# Ver_Full.net
KiCad netlist of a schematic drawn in EAGLE
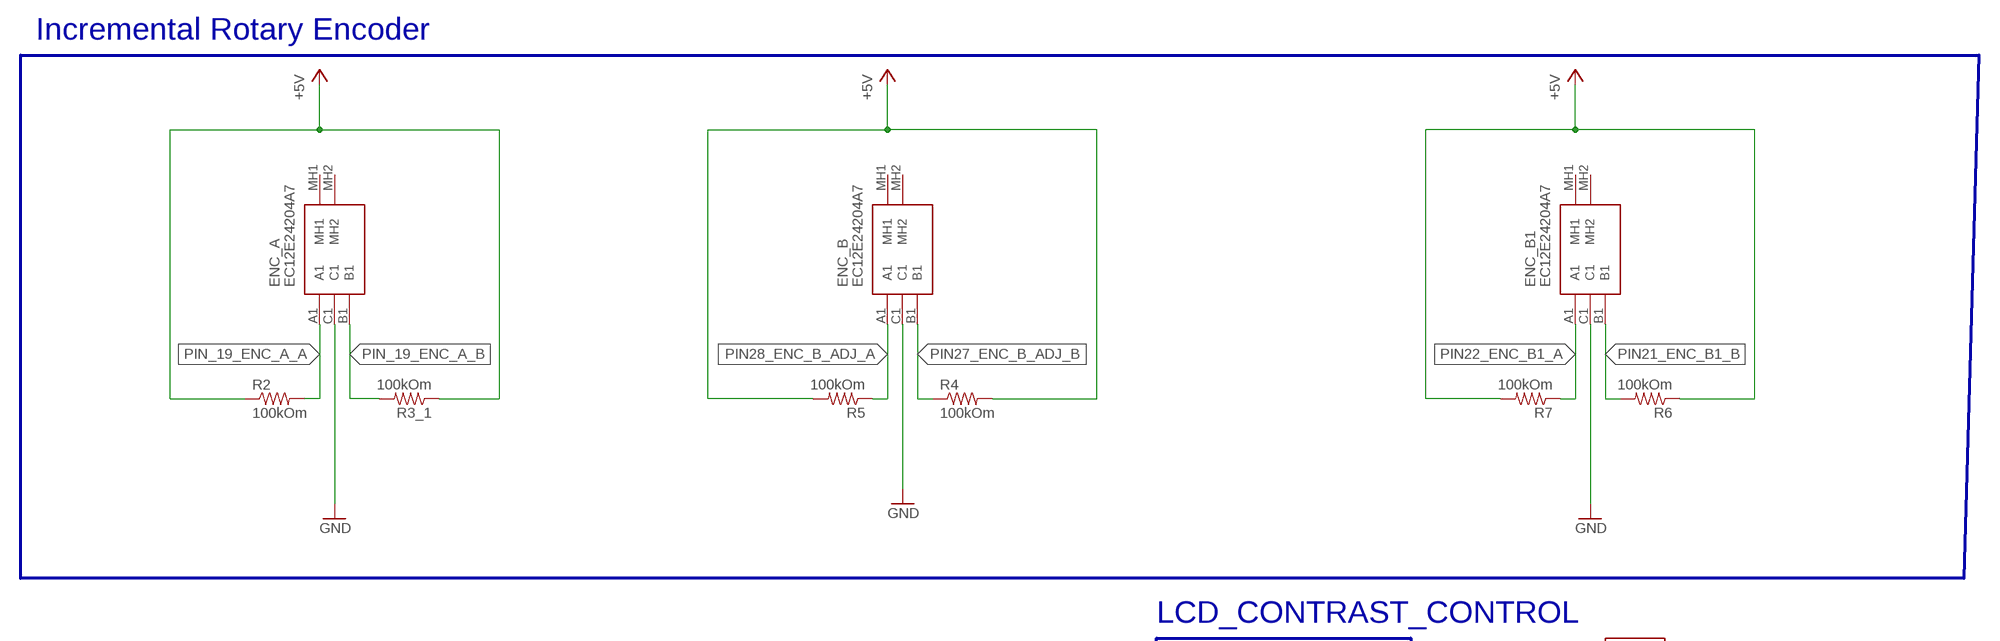
[diagram p0: schematic, sheet 1, part 1 of 3]
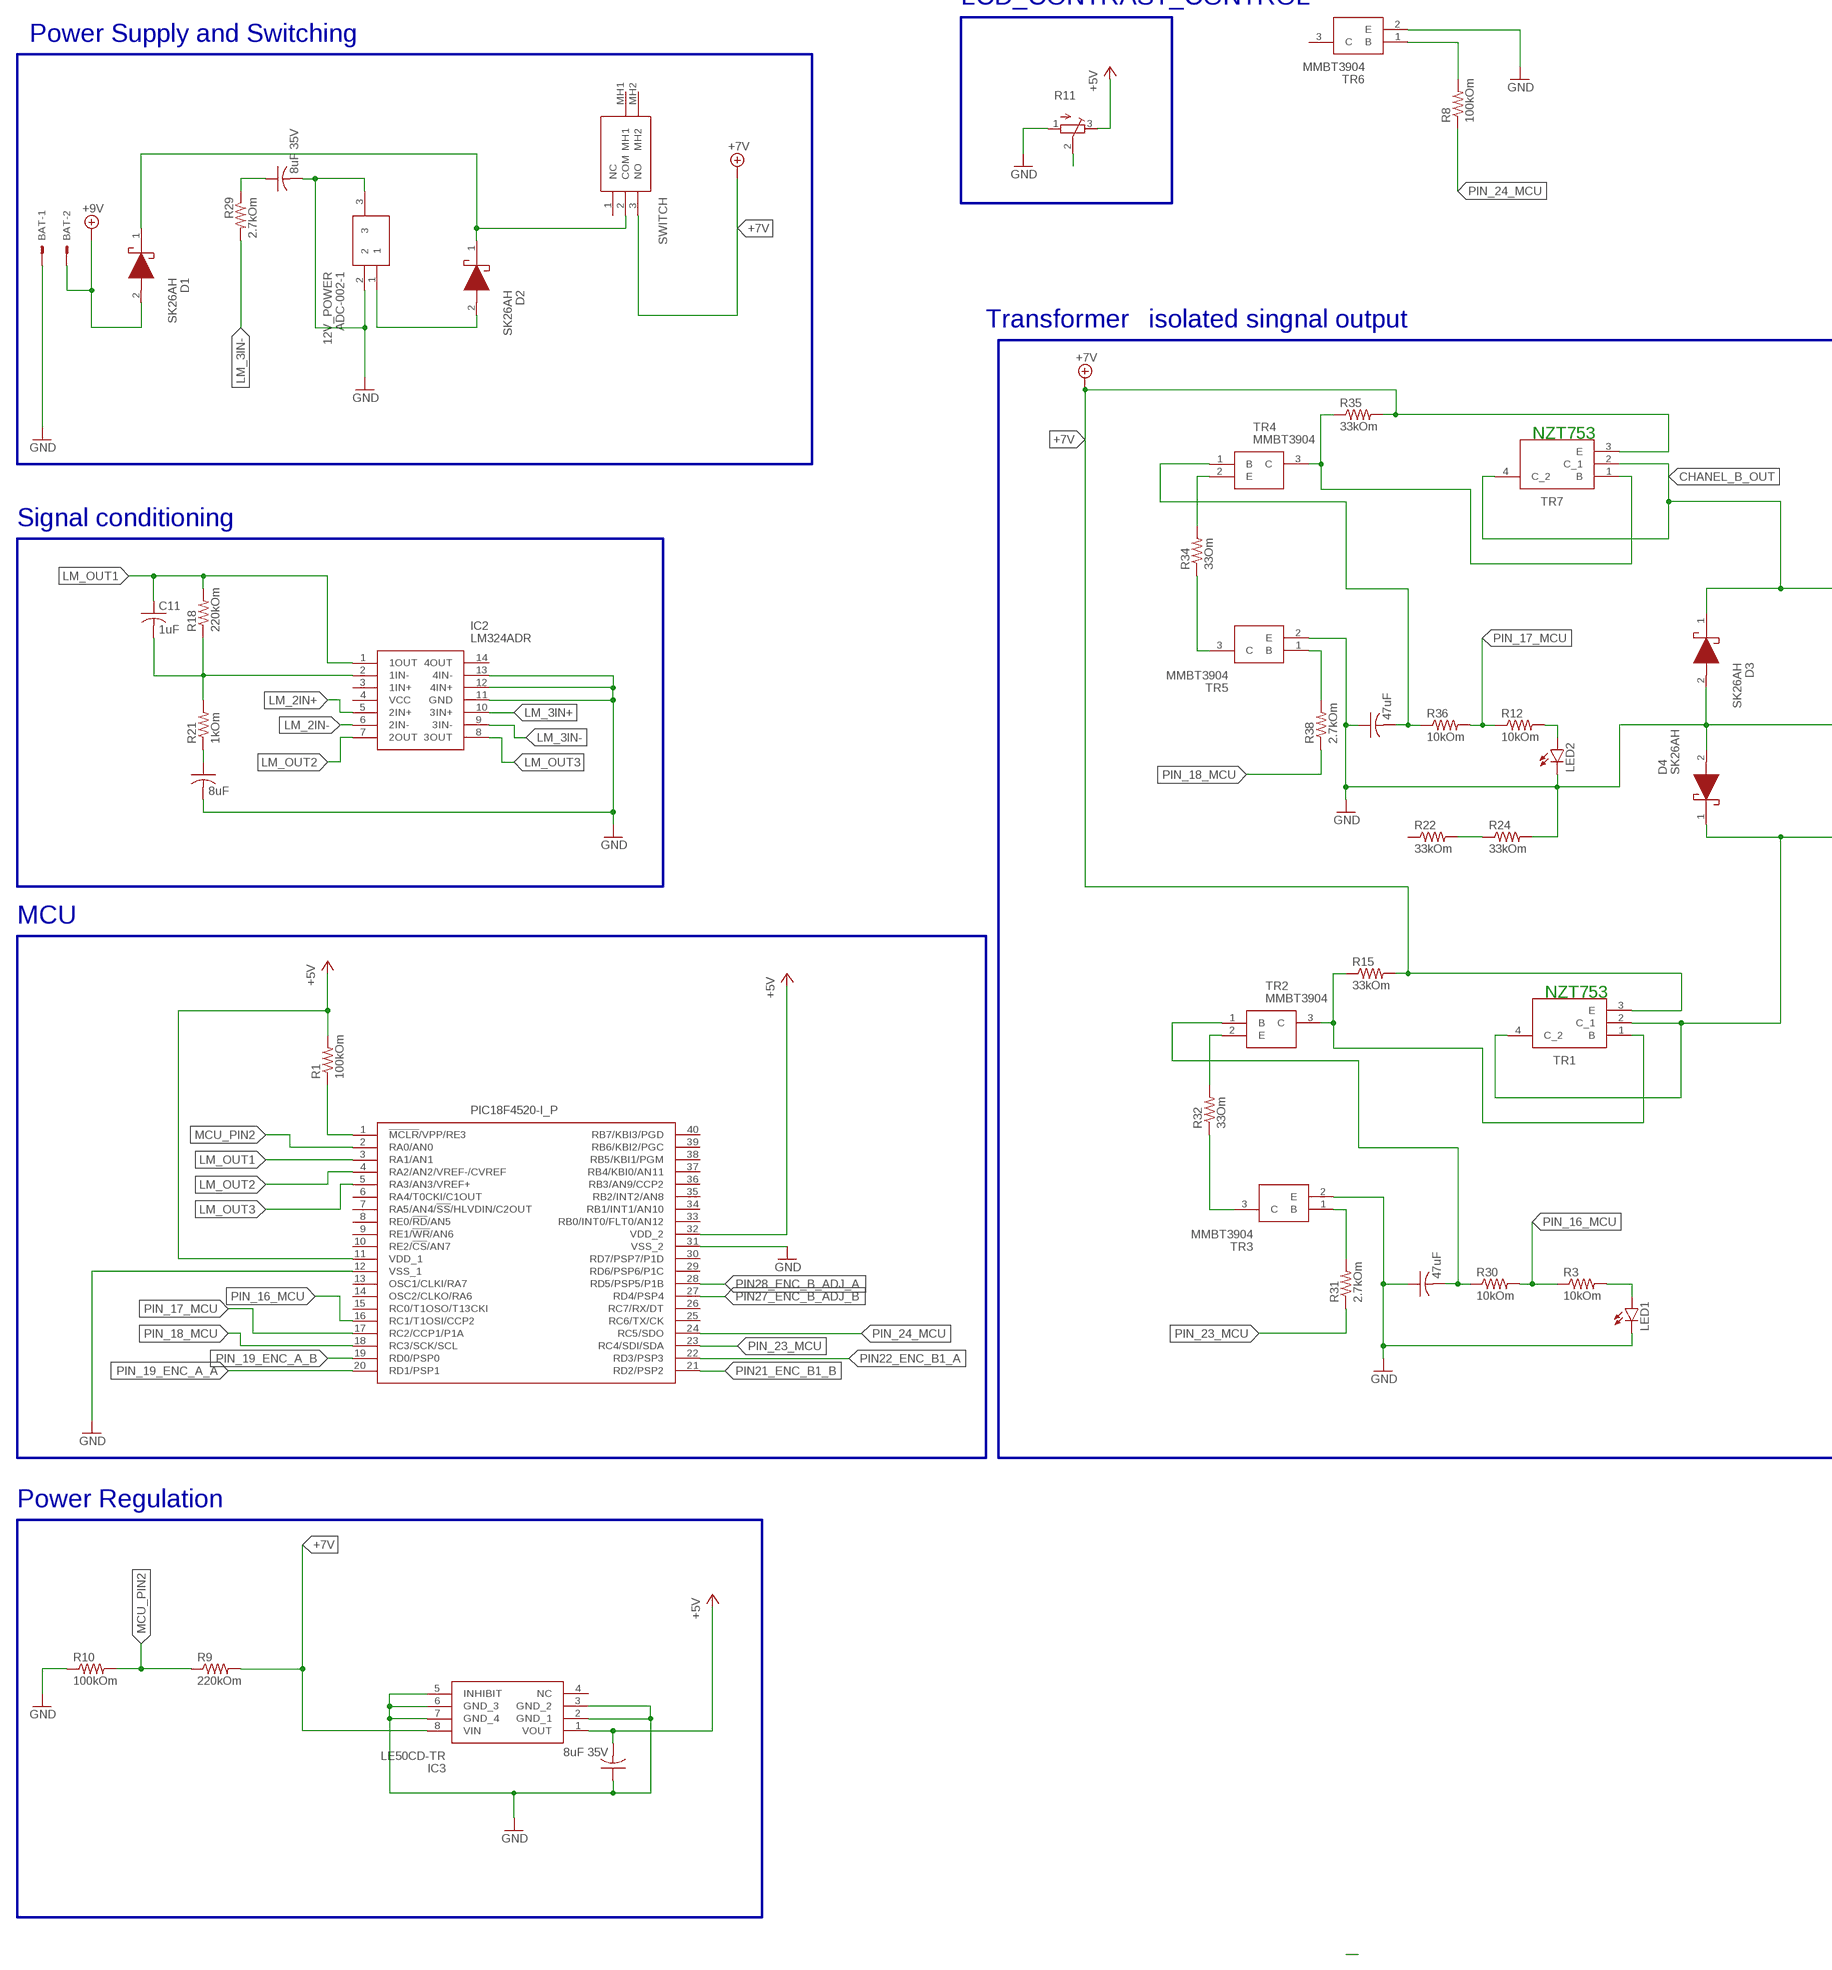
[diagram p1: schematic, sheet 1, part 2 of 3]
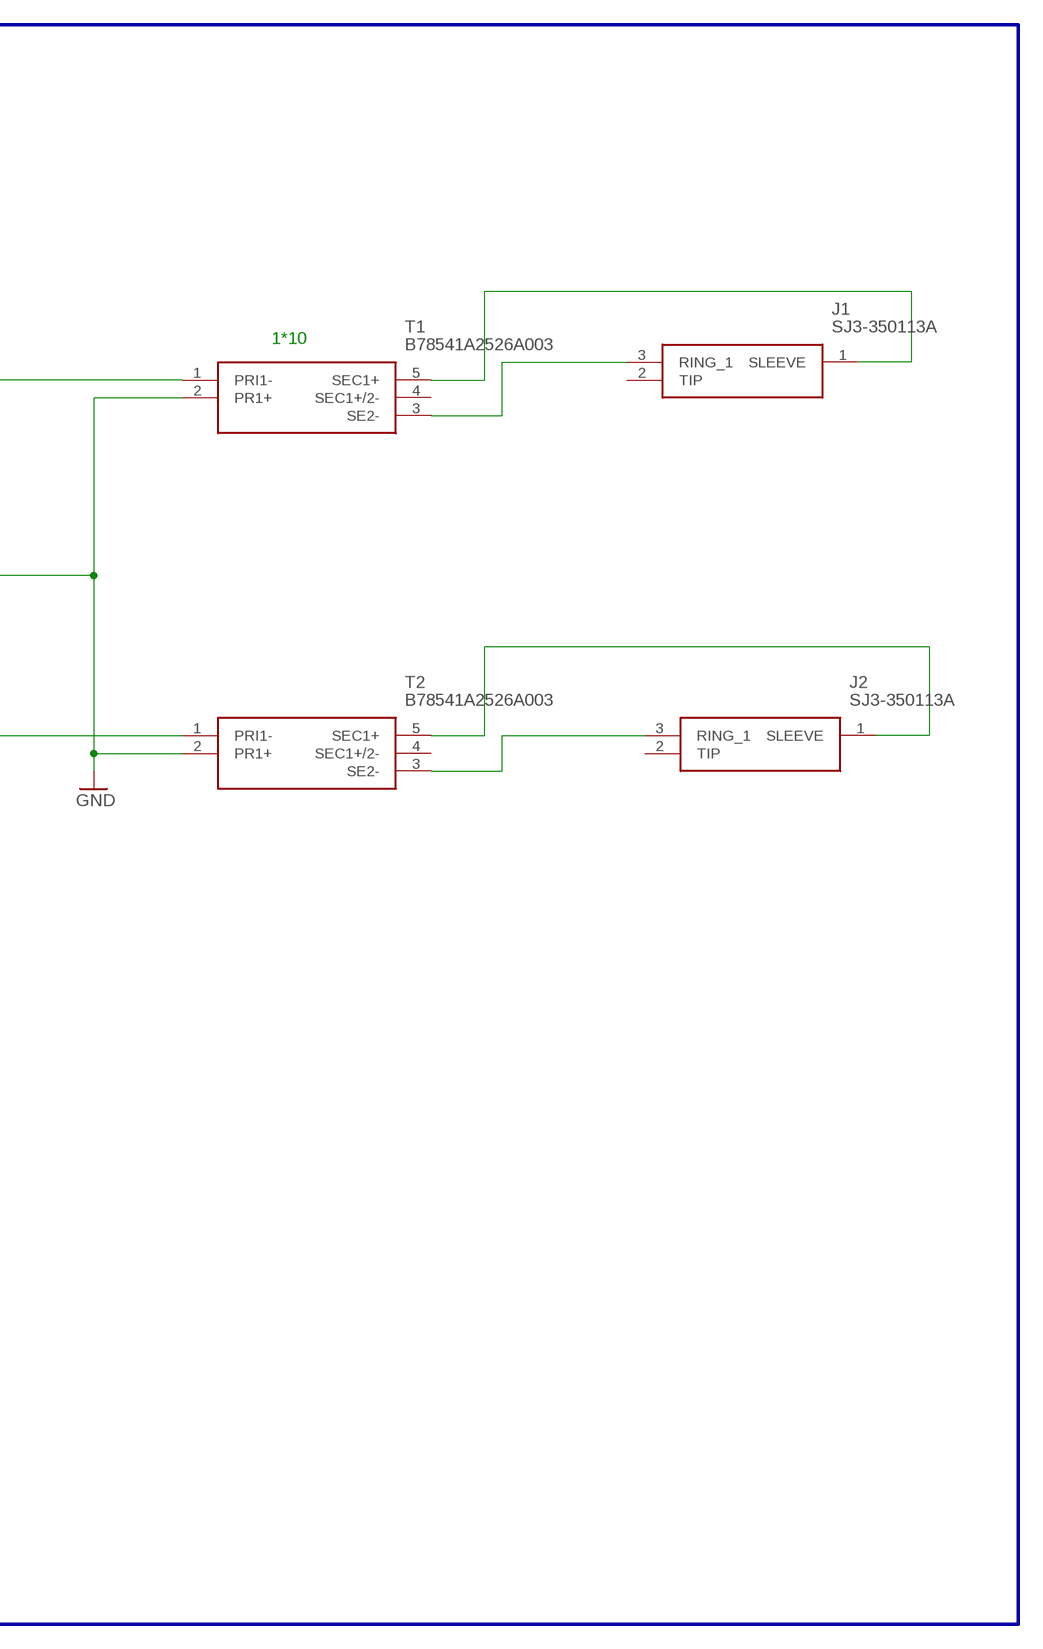
[diagram p2: schematic, sheet 1, part 3 of 3]
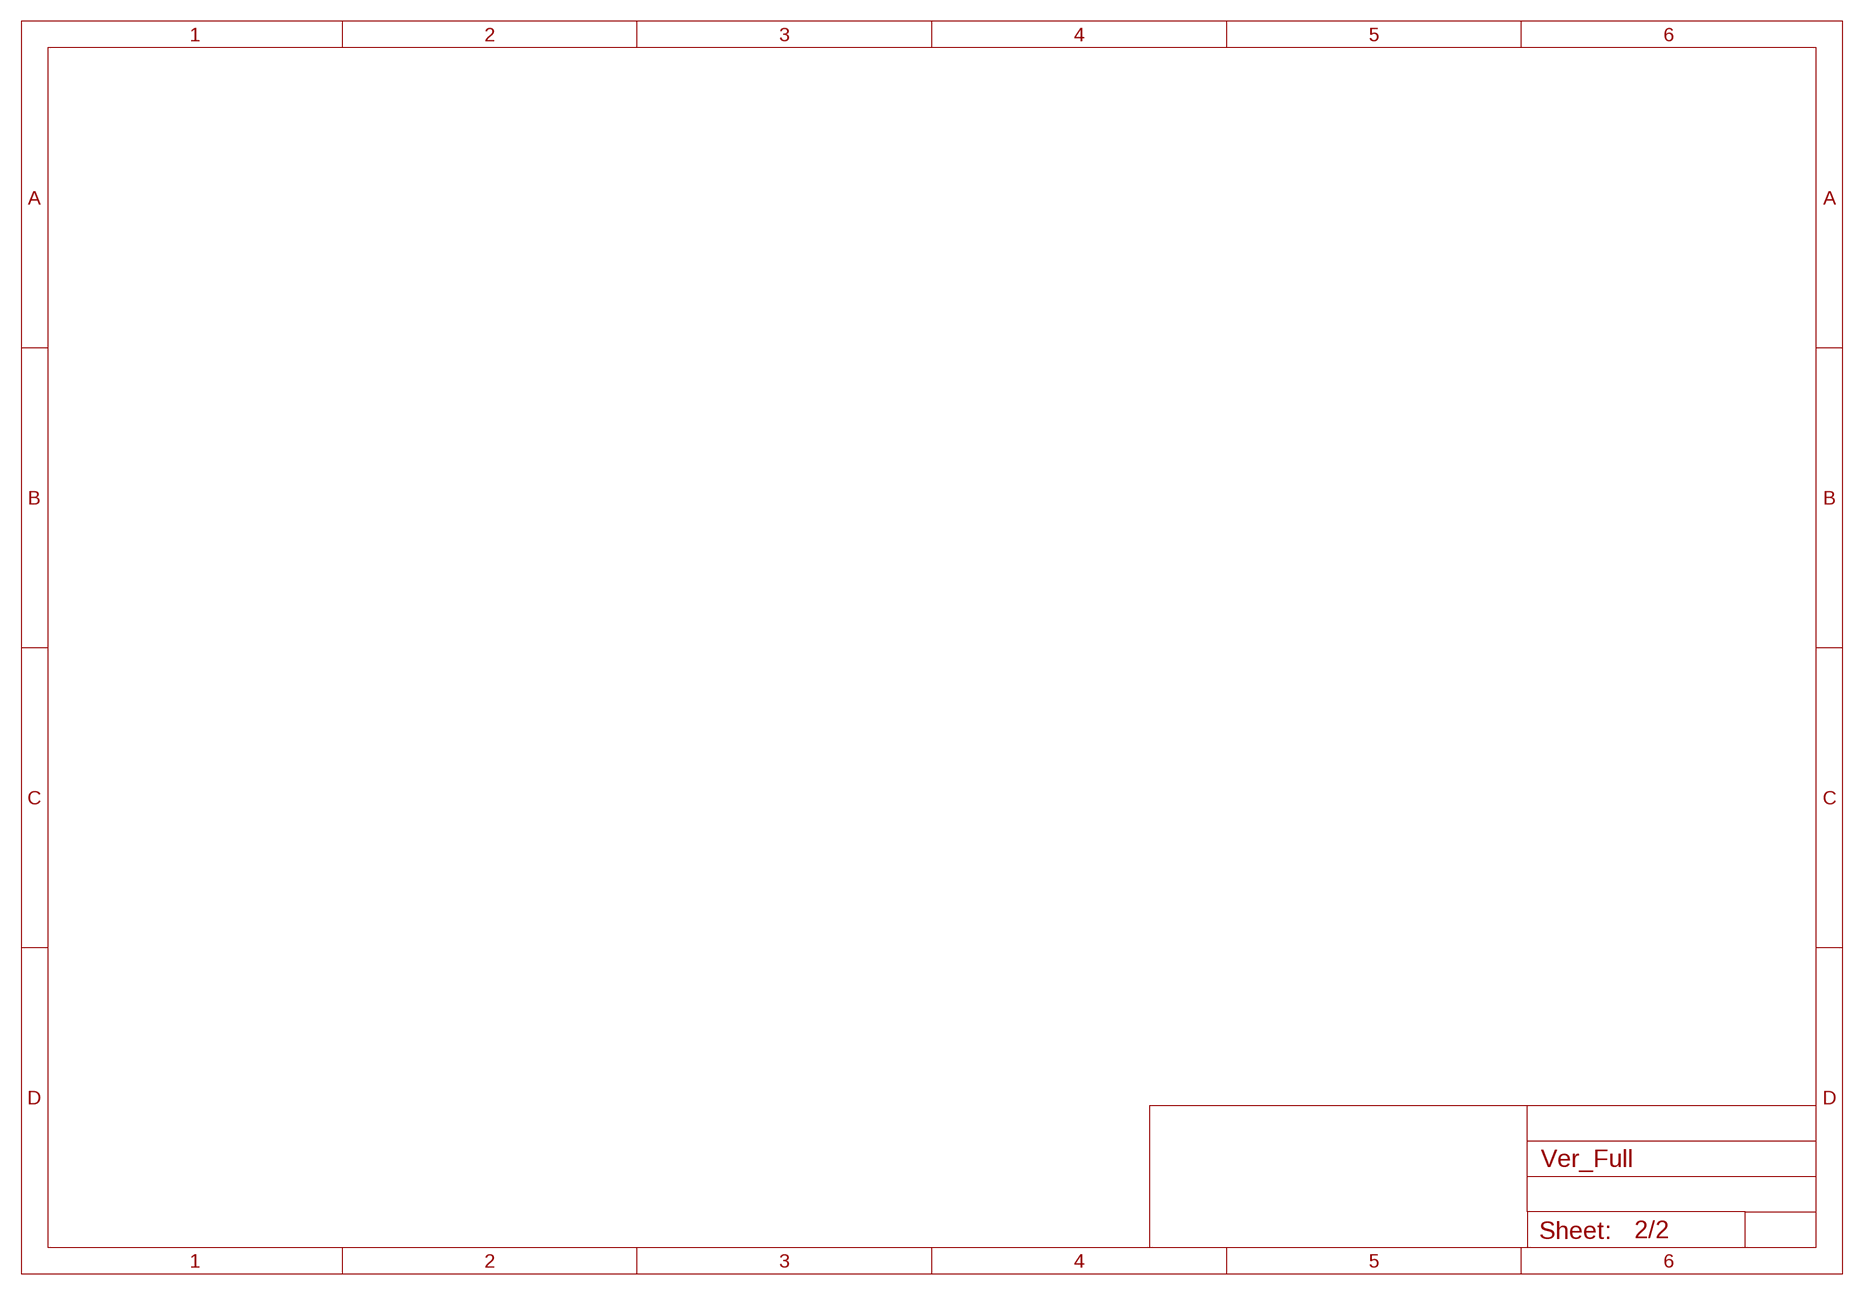
[diagram p3: schematic, sheet 2]

(export (version "E")
  (design (tool "Eeschema 10.0.6"))
  (components
    (comp (ref "12V_POWER")
      (value "ADC-002-1")
      (footprint "eagle-import:ADC0021")
      (fields (field (name "MOUSER_PART_NUMBER") "737-ADC-002-1"))
      (libsource (lib "eagle-import") (part "ADC-002-1"))
    )
    (comp (ref "BAT")
      (value "22-23-2021")
      (footprint "eagle-import:22-23-2021")
      (fields (field (name "MF") "MOLEX"))
      (libsource (lib "eagle-import") (part "22-23-2021"))
    )
    (comp (ref "C2")
      (value "8uF 35V")
      (footprint "eagle-import:C1608")
      (libsource (lib "eagle-import") (part "C-USC1608"))
    )
    (comp (ref "C3_1")
      (value "8uF 35V")
      (footprint "eagle-import:C1608")
      (libsource (lib "eagle-import") (part "C-USC1608"))
    )
    (comp (ref "C6")
      (value "8uF")
      (footprint "eagle-import:C1608")
      (libsource (lib "eagle-import") (part "C-USC1608"))
    )
    (comp (ref "C11")
      (value "1uF")
      (footprint "eagle-import:C0603")
      (libsource (lib "eagle-import") (part "C-USC0603"))
    )
    (comp (ref "C14")
      (value "47uF")
      (footprint "eagle-import:C1608")
      (libsource (lib "eagle-import") (part "C-USC1608"))
    )
    (comp (ref "C16")
      (value "47uF")
      (footprint "eagle-import:C1608")
      (libsource (lib "eagle-import") (part "C-USC1608"))
    )
    (comp (ref "D1")
      (value "SK26AH")
      (footprint "eagle-import:DIONM5126X250N")
      (fields (field (name "MOUSER_PART_NUMBER") "821-SK26AH"))
      (libsource (lib "eagle-import") (part "SK26AH"))
    )
    (comp (ref "D2")
      (value "SK26AH")
      (footprint "eagle-import:DIONM5126X250N")
      (fields (field (name "MOUSER_PART_NUMBER") "821-SK26AH"))
      (libsource (lib "eagle-import") (part "SK26AH"))
    )
    (comp (ref "D3")
      (value "SK26AH")
      (footprint "eagle-import:DIONM5126X250N")
      (fields (field (name "MOUSER_PART_NUMBER") "821-SK26AH"))
      (libsource (lib "eagle-import") (part "SK26AH"))
    )
    (comp (ref "D4")
      (value "SK26AH")
      (footprint "eagle-import:DIONM5126X250N")
      (fields (field (name "MOUSER_PART_NUMBER") "821-SK26AH"))
      (libsource (lib "eagle-import") (part "SK26AH"))
    )
    (comp (ref "ENC_A")
      (value "EC12E24204A7")
      (footprint "eagle-import:EC12E24204A7")
      (fields (field (name "MOUSER_PART_NUMBER") "688-EC12E24204A7"))
      (libsource (lib "eagle-import") (part "EC12E24204A7"))
    )
    (comp (ref "ENC_B")
      (value "EC12E24204A7")
      (footprint "eagle-import:EC12E24204A7")
      (fields (field (name "MOUSER_PART_NUMBER") "688-EC12E24204A7"))
      (libsource (lib "eagle-import") (part "EC12E24204A7"))
    )
    (comp (ref "ENC_B1")
      (value "EC12E24204A7")
      (footprint "eagle-import:EC12E24204A7")
      (fields (field (name "MOUSER_PART_NUMBER") "688-EC12E24204A7"))
      (libsource (lib "eagle-import") (part "EC12E24204A7"))
    )
    (comp (ref "IC1")
      (value "PIC18F4520-I_P")
      (footprint "eagle-import:DIP1778W58P254L5175H635Q40N")
      (fields
        (field (name "MANUFACTURER_PART_NUMBER") "PIC18F4520-I/P")
        (field (name "MOUSER_PART_NUMBER") "579-PIC18F4520-I/P")
      )
      (libsource (lib "eagle-import") (part "PIC18F4520-I_P"))
    )
    (comp (ref "IC2")
      (value "LM324ADR")
      (footprint "eagle-import:SOIC127P600X175-14N")
      (fields (field (name "MOUSER_PART_NUMBER") "595-LM324ADR"))
      (libsource (lib "eagle-import") (part "LM324ADR"))
    )
    (comp (ref "IC3")
      (value "LE50CD-TR")
      (footprint "eagle-import:SOIC127P600X175-8N")
      (fields (field (name "MOUSER_PART_NUMBER") "511-LE50CD-TR"))
      (libsource (lib "eagle-import") (part "LE50CD-TR"))
    )
    (comp (ref "J1")
      (value "SJ3-350113A")
      (footprint "eagle-import:SJ3350113A")
      (libsource (lib "eagle-import") (part "SJ3-350113A"))
    )
    (comp (ref "J2")
      (value "SJ3-350113A")
      (footprint "eagle-import:SJ3350113A")
      (libsource (lib "eagle-import") (part "SJ3-350113A"))
    )
    (comp (ref "LED1")
      (value "LAP4-BOTTOM")
      (footprint "eagle-import:P47F-BOTTOM")
      (libsource (lib "eagle-import") (part "P4-BOTTOMLA"))
    )
    (comp (ref "LED2")
      (value "LAP4-BOTTOM")
      (footprint "eagle-import:P47F-BOTTOM")
      (libsource (lib "eagle-import") (part "P4-BOTTOMLA"))
    )
    (comp (ref "R1")
      (value "100kOm")
      (footprint "eagle-import:R0402")
      (libsource (lib "eagle-import") (part "R-US_R0402"))
    )
    (comp (ref "R2")
      (value "100kOm")
      (footprint "eagle-import:R0402")
      (libsource (lib "eagle-import") (part "R-US_R0402"))
    )
    (comp (ref "R3")
      (value "10kOm")
      (footprint "eagle-import:R0402")
      (libsource (lib "eagle-import") (part "R-US_R0402"))
    )
    (comp (ref "R3_1")
      (value "100kOm")
      (footprint "eagle-import:R0402")
      (libsource (lib "eagle-import") (part "R-US_R0402"))
    )
    (comp (ref "R4")
      (value "100kOm")
      (footprint "eagle-import:R0402")
      (libsource (lib "eagle-import") (part "R-US_R0402"))
    )
    (comp (ref "R5")
      (value "100kOm")
      (footprint "eagle-import:R0402")
      (libsource (lib "eagle-import") (part "R-US_R0402"))
    )
    (comp (ref "R6")
      (value "100kOm")
      (footprint "eagle-import:R0402")
      (libsource (lib "eagle-import") (part "R-US_R0402"))
    )
    (comp (ref "R7")
      (value "100kOm")
      (footprint "eagle-import:R0402")
      (libsource (lib "eagle-import") (part "R-US_R0402"))
    )
    (comp (ref "R8")
      (value "100kOm")
      (footprint "eagle-import:R0402")
      (libsource (lib "eagle-import") (part "R-US_R0402"))
    )
    (comp (ref "R9")
      (value "220kOm")
      (footprint "eagle-import:R0402")
      (libsource (lib "eagle-import") (part "R-US_R0402"))
    )
    (comp (ref "R10")
      (value "100kOm")
      (footprint "eagle-import:R0402")
      (libsource (lib "eagle-import") (part "R-US_R0402"))
    )
    (comp (ref "R11")
      (value "R-TRIMM4G/J")
      (footprint "eagle-import:RTRIM4G_J")
      (libsource (lib "eagle-import") (part "R-TRIMM4G/J"))
    )
    (comp (ref "R12")
      (value "10kOm")
      (footprint "eagle-import:R0402")
      (libsource (lib "eagle-import") (part "R-US_R0402"))
    )
    (comp (ref "R15")
      (value "33kOm")
      (footprint "eagle-import:R0402")
      (libsource (lib "eagle-import") (part "R-US_R0402"))
    )
    (comp (ref "R18")
      (value "220kOm")
      (footprint "eagle-import:R0402")
      (libsource (lib "eagle-import") (part "R-US_R0402"))
    )
    (comp (ref "R21")
      (value "1kOm")
      (footprint "eagle-import:R0402")
      (libsource (lib "eagle-import") (part "R-US_R0402"))
    )
    (comp (ref "R22")
      (value "33kOm")
      (footprint "eagle-import:R0402")
      (libsource (lib "eagle-import") (part "R-US_R0402"))
    )
    (comp (ref "R24")
      (value "33kOm")
      (footprint "eagle-import:R0402")
      (libsource (lib "eagle-import") (part "R-US_R0402"))
    )
    (comp (ref "R29")
      (value "2.7kOm")
      (footprint "eagle-import:R0402")
      (libsource (lib "eagle-import") (part "R-US_R0402"))
    )
    (comp (ref "R30")
      (value "10kOm")
      (footprint "eagle-import:R0402")
      (libsource (lib "eagle-import") (part "R-US_R0402"))
    )
    (comp (ref "R31")
      (value "2.7kOm")
      (footprint "eagle-import:R0402")
      (libsource (lib "eagle-import") (part "R-US_R0402"))
    )
    (comp (ref "R32")
      (value "33Om")
      (footprint "eagle-import:R0402")
      (libsource (lib "eagle-import") (part "R-US_R0402"))
    )
    (comp (ref "R34")
      (value "33Om")
      (footprint "eagle-import:R0402")
      (libsource (lib "eagle-import") (part "R-US_R0402"))
    )
    (comp (ref "R35")
      (value "33kOm")
      (footprint "eagle-import:R0402")
      (libsource (lib "eagle-import") (part "R-US_R0402"))
    )
    (comp (ref "R36")
      (value "10kOm")
      (footprint "eagle-import:R0402")
      (libsource (lib "eagle-import") (part "R-US_R0402"))
    )
    (comp (ref "R38")
      (value "2.7kOm")
      (footprint "eagle-import:R0402")
      (libsource (lib "eagle-import") (part "R-US_R0402"))
    )
    (comp (ref "S1")
      (value "SWITCH")
      (footprint "eagle-import:5MS1S102AM6QES")
      (fields
        (field (name "MANUFACTURER_PART_NUMBER") "5MS1S102AM6QES")
        (field (name "MOUSER_PART_NUMBER") "118-5MS1S102AM6QES")
      )
      (libsource (lib "eagle-import") (part "5MS1S102AM6QES"))
    )
    (comp (ref "T1")
      (value "B78541A2526A003")
      (footprint "eagle-import:B78541A2526A003")
      (libsource (lib "eagle-import") (part "B78541A2526A003"))
    )
    (comp (ref "T2")
      (value "B78541A2526A003")
      (footprint "eagle-import:B78541A2526A003")
      (libsource (lib "eagle-import") (part "B78541A2526A003"))
    )
    (comp (ref "TR1")
      (value "NSS60600MZ4T1G")
      (footprint "eagle-import:SOT230P700X175-4N")
      (fields (field (name "MOUSER_PART_NUMBER") "863-NSS60600MZ4T1G"))
      (libsource (lib "eagle-import") (part "NSS60600MZ4T1G"))
    )
    (comp (ref "TR2")
      (value "MMBT3904")
      (footprint "eagle-import:SOT95P240X120-3N")
      (fields (field (name "MOUSER_PART_NUMBER") "637-MMBT3904"))
      (libsource (lib "eagle-import") (part "MMBT3904"))
    )
    (comp (ref "TR3")
      (value "MMBT3904")
      (footprint "eagle-import:SOT95P240X120-3N")
      (fields (field (name "MOUSER_PART_NUMBER") "637-MMBT3904"))
      (libsource (lib "eagle-import") (part "MMBT3904"))
    )
    (comp (ref "TR4")
      (value "MMBT3904")
      (footprint "eagle-import:SOT95P240X120-3N")
      (fields (field (name "MOUSER_PART_NUMBER") "637-MMBT3904"))
      (libsource (lib "eagle-import") (part "MMBT3904"))
    )
    (comp (ref "TR5")
      (value "MMBT3904")
      (footprint "eagle-import:SOT95P240X120-3N")
      (fields (field (name "MOUSER_PART_NUMBER") "637-MMBT3904"))
      (libsource (lib "eagle-import") (part "MMBT3904"))
    )
    (comp (ref "TR6")
      (value "MMBT3904")
      (footprint "eagle-import:SOT95P240X120-3N")
      (fields (field (name "MOUSER_PART_NUMBER") "637-MMBT3904"))
      (libsource (lib "eagle-import") (part "MMBT3904"))
    )
    (comp (ref "TR7")
      (value "NSS60600MZ4T1G")
      (footprint "eagle-import:SOT230P700X175-4N")
      (fields (field (name "MOUSER_PART_NUMBER") "863-NSS60600MZ4T1G"))
      (libsource (lib "eagle-import") (part "NSS60600MZ4T1G"))
    )
  )
  (nets
    (net (code "1") (name "+5V") (class "Default")
      (node (ref "C3_1") (pin "2") (pinfunction "2_2") (pintype "passive"))
      (node (ref "IC1") (pin "11") (pinfunction "VDD_1_11") (pintype "bidirectional"))
      (node (ref "IC1") (pin "32") (pinfunction "VDD_2_32") (pintype "bidirectional"))
      (node (ref "IC3") (pin "1") (pinfunction "VOUT_1") (pintype "bidirectional"))
      (node (ref "R1") (pin "2") (pinfunction "2_2") (pintype "passive"))
      (node (ref "R11") (pin "3") (pinfunction "E_3") (pintype "passive"))
      (node (ref "R2") (pin "1") (pinfunction "1_1") (pintype "passive"))
      (node (ref "R3_1") (pin "1") (pinfunction "1_1") (pintype "passive"))
      (node (ref "R4") (pin "2") (pinfunction "2_2") (pintype "passive"))
      (node (ref "R5") (pin "2") (pinfunction "2_2") (pintype "passive"))
      (node (ref "R6") (pin "1") (pinfunction "1_1") (pintype "passive"))
      (node (ref "R7") (pin "2") (pinfunction "2_2") (pintype "passive"))
    )
    (net (code "2") (name "+7V") (class "Default")
      (node (ref "IC3") (pin "8") (pinfunction "VIN_8") (pintype "bidirectional"))
      (node (ref "R15") (pin "2") (pinfunction "2_2") (pintype "passive"))
      (node (ref "R35") (pin "2") (pinfunction "2_2") (pintype "passive"))
      (node (ref "R9") (pin "2") (pinfunction "2_2") (pintype "passive"))
      (node (ref "S1") (pin "3") (pinfunction "NO_3") (pintype "bidirectional"))
      (node (ref "TR1") (pin "3") (pinfunction "E_3") (pintype "bidirectional"))
      (node (ref "TR7") (pin "3") (pinfunction "E_3") (pintype "bidirectional"))
    )
    (net (code "3") (name "+9V") (class "Default")
      (node (ref "BAT") (pin "2") (pinfunction "S_2") (pintype "passive"))
      (node (ref "D1") (pin "2") (pinfunction "A_2") (pintype "bidirectional"))
    )
    (net (code "4") (name "CHANEL_B_OUT") (class "Default")
      (node (ref "D3") (pin "1") (pinfunction "K_1") (pintype "bidirectional"))
      (node (ref "T1") (pin "1") (pinfunction "PRI1-_1") (pintype "bidirectional"))
      (node (ref "TR7") (pin "2") (pinfunction "C_1_2") (pintype "bidirectional"))
      (node (ref "TR7") (pin "4") (pinfunction "C_2_4") (pintype "bidirectional"))
    )
    (net (code "5") (name "GND") (class "Default")
      (node (ref "12V_POWER") (pin "2") (pinfunction "2_2") (pintype "bidirectional"))
      (node (ref "12V_POWER") (pin "3") (pinfunction "3_3") (pintype "bidirectional"))
      (node (ref "BAT") (pin "1") (pinfunction "S_1") (pintype "passive"))
      (node (ref "C14") (pin "1") (pinfunction "1_1") (pintype "passive"))
      (node (ref "C16") (pin "1") (pinfunction "1_1") (pintype "passive"))
      (node (ref "C2") (pin "2") (pinfunction "2_2") (pintype "passive"))
      (node (ref "C3_1") (pin "1") (pinfunction "1_1") (pintype "passive"))
      (node (ref "C6") (pin "2") (pinfunction "2_2") (pintype "passive"))
      (node (ref "D3") (pin "2") (pinfunction "A_2") (pintype "bidirectional"))
      (node (ref "D4") (pin "2") (pinfunction "A_2") (pintype "bidirectional"))
      (node (ref "ENC_A") (pin "C1") (pinfunction "C1_C1") (pintype "bidirectional"))
      (node (ref "ENC_B") (pin "C1") (pinfunction "C1_C1") (pintype "bidirectional"))
      (node (ref "ENC_B1") (pin "C1") (pinfunction "C1_C1") (pintype "bidirectional"))
      (node (ref "IC1") (pin "12") (pinfunction "VSS_1_12") (pintype "bidirectional"))
      (node (ref "IC1") (pin "31") (pinfunction "VSS_2_31") (pintype "bidirectional"))
      (node (ref "IC2") (pin "11") (pinfunction "GND_11") (pintype "bidirectional"))
      (node (ref "IC2") (pin "12") (pinfunction "4IN+_12") (pintype "bidirectional"))
      (node (ref "IC2") (pin "13") (pinfunction "4IN-_13") (pintype "bidirectional"))
      (node (ref "IC3") (pin "2") (pinfunction "GND_1_2") (pintype "bidirectional"))
      (node (ref "IC3") (pin "3") (pinfunction "GND_2_3") (pintype "bidirectional"))
      (node (ref "IC3") (pin "5") (pinfunction "INHIBIT_5") (pintype "bidirectional"))
      (node (ref "IC3") (pin "6") (pinfunction "GND_3_6") (pintype "bidirectional"))
      (node (ref "IC3") (pin "7") (pinfunction "GND_4_7") (pintype "bidirectional"))
      (node (ref "LED1") (pin "C") (pinfunction "C_C") (pintype "passive"))
      (node (ref "LED2") (pin "C") (pinfunction "C_C") (pintype "passive"))
      (node (ref "R10") (pin "1") (pinfunction "1_1") (pintype "passive"))
      (node (ref "R11") (pin "1") (pinfunction "A_1") (pintype "passive"))
      (node (ref "R24") (pin "2") (pinfunction "2_2") (pintype "passive"))
      (node (ref "T1") (pin "2") (pinfunction "PR1+_2") (pintype "bidirectional"))
      (node (ref "T2") (pin "2") (pinfunction "PR1+_2") (pintype "bidirectional"))
      (node (ref "TR3") (pin "2") (pinfunction "E_2") (pintype "bidirectional"))
      (node (ref "TR5") (pin "2") (pinfunction "E_2") (pintype "bidirectional"))
      (node (ref "TR6") (pin "2") (pinfunction "E_2") (pintype "bidirectional"))
    )
    (net (code "6") (name "LM_2IN+") (class "Default")
      (node (ref "IC2") (pin "5") (pinfunction "2IN+_5") (pintype "bidirectional"))
    )
    (net (code "7") (name "LM_2IN-") (class "Default")
      (node (ref "IC2") (pin "6") (pinfunction "2IN-_6") (pintype "bidirectional"))
    )
    (net (code "8") (name "LM_3IN+") (class "Default")
      (node (ref "IC2") (pin "10") (pinfunction "3IN+_10") (pintype "bidirectional"))
    )
    (net (code "9") (name "LM_3IN-") (class "Default")
      (node (ref "IC2") (pin "9") (pinfunction "3IN-_9") (pintype "bidirectional"))
      (node (ref "R29") (pin "2") (pinfunction "2_2") (pintype "passive"))
    )
    (net (code "10") (name "LM_OUT1") (class "Default")
      (node (ref "C11") (pin "1") (pinfunction "1_1") (pintype "passive"))
      (node (ref "IC1") (pin "3") (pinfunction "RA1/AN1_3") (pintype "bidirectional"))
      (node (ref "IC2") (pin "1") (pinfunction "1OUT_1") (pintype "bidirectional"))
      (node (ref "R18") (pin "2") (pinfunction "2_2") (pintype "passive"))
    )
    (net (code "11") (name "LM_OUT2") (class "Default")
      (node (ref "IC1") (pin "4") (pinfunction "RA2/AN2/VREF-/CVREF_4") (pintype "bidirectional"))
      (node (ref "IC2") (pin "7") (pinfunction "2OUT_7") (pintype "bidirectional"))
    )
    (net (code "12") (name "LM_OUT3") (class "Default")
      (node (ref "IC1") (pin "5") (pinfunction "RA3/AN3/VREF+_5") (pintype "bidirectional"))
      (node (ref "IC2") (pin "8") (pinfunction "3OUT_8") (pintype "bidirectional"))
    )
    (net (code "13") (name "MCU_PIN2") (class "Default")
      (node (ref "IC1") (pin "2") (pinfunction "RA0/AN0_2") (pintype "bidirectional"))
      (node (ref "R10") (pin "2") (pinfunction "2_2") (pintype "passive"))
      (node (ref "R9") (pin "1") (pinfunction "1_1") (pintype "passive"))
    )
    (net (code "14") (name "Net-(C2-Pad1)") (class "Default")
      (node (ref "C2") (pin "1") (pinfunction "1_1") (pintype "passive"))
      (node (ref "R29") (pin "1") (pinfunction "1_1") (pintype "passive"))
    )
    (net (code "15") (name "Net-(C6-Pad1)") (class "Default")
      (node (ref "C6") (pin "1") (pinfunction "1_1") (pintype "passive"))
      (node (ref "R21") (pin "1") (pinfunction "1_1") (pintype "passive"))
    )
    (net (code "16") (name "Net-(D1-K)") (class "Default")
      (node (ref "D1") (pin "1") (pinfunction "K_1") (pintype "bidirectional"))
      (node (ref "D2") (pin "1") (pinfunction "K_1") (pintype "bidirectional"))
      (node (ref "S1") (pin "2") (pinfunction "COM_2") (pintype "bidirectional"))
    )
    (net (code "17") (name "Net-(D2-A)") (class "Default")
      (node (ref "12V_POWER") (pin "1") (pinfunction "1_1") (pintype "bidirectional"))
      (node (ref "D2") (pin "2") (pinfunction "A_2") (pintype "bidirectional"))
    )
    (net (code "18") (name "Net-(D4-K)") (class "Default")
      (node (ref "D4") (pin "1") (pinfunction "K_1") (pintype "bidirectional"))
      (node (ref "T2") (pin "1") (pinfunction "PRI1-_1") (pintype "bidirectional"))
      (node (ref "TR1") (pin "2") (pinfunction "C_1_2") (pintype "bidirectional"))
      (node (ref "TR1") (pin "4") (pinfunction "C_2_4") (pintype "bidirectional"))
    )
    (net (code "19") (name "Net-(IC1-~{MCLR}{slash}VPP{slash}RE3)") (class "Default")
      (node (ref "IC1") (pin "1") (pinfunction "~{MCLR}/VPP/RE3_1") (pintype "bidirectional"))
      (node (ref "R1") (pin "1") (pinfunction "1_1") (pintype "passive"))
    )
    (net (code "20") (name "Net-(IC2-1IN-)") (class "Default")
      (node (ref "C11") (pin "2") (pinfunction "2_2") (pintype "passive"))
      (node (ref "IC2") (pin "2") (pinfunction "1IN-_2") (pintype "bidirectional"))
      (node (ref "R18") (pin "1") (pinfunction "1_1") (pintype "passive"))
      (node (ref "R21") (pin "2") (pinfunction "2_2") (pintype "passive"))
    )
    (net (code "21") (name "Net-(J1-RING_1)") (class "Default")
      (node (ref "J1") (pin "3") (pinfunction "RING_1_3") (pintype "bidirectional"))
      (node (ref "T1") (pin "3") (pinfunction "SE2-_3") (pintype "bidirectional"))
    )
    (net (code "22") (name "Net-(J1-SLEEVE)") (class "Default")
      (node (ref "J1") (pin "1") (pinfunction "SLEEVE_1") (pintype "bidirectional"))
      (node (ref "T1") (pin "5") (pinfunction "SEC1+_5") (pintype "bidirectional"))
    )
    (net (code "23") (name "Net-(J2-RING_1)") (class "Default")
      (node (ref "J2") (pin "3") (pinfunction "RING_1_3") (pintype "bidirectional"))
      (node (ref "T2") (pin "3") (pinfunction "SE2-_3") (pintype "bidirectional"))
    )
    (net (code "24") (name "Net-(J2-SLEEVE)") (class "Default")
      (node (ref "J2") (pin "1") (pinfunction "SLEEVE_1") (pintype "bidirectional"))
      (node (ref "T2") (pin "5") (pinfunction "SEC1+_5") (pintype "bidirectional"))
    )
    (net (code "25") (name "Net-(LED1-PadA)") (class "Default")
      (node (ref "LED1") (pin "A") (pinfunction "A_A") (pintype "passive"))
      (node (ref "R3") (pin "2") (pinfunction "2_2") (pintype "passive"))
    )
    (net (code "26") (name "Net-(LED2-PadA)") (class "Default")
      (node (ref "LED2") (pin "A") (pinfunction "A_A") (pintype "passive"))
      (node (ref "R12") (pin "2") (pinfunction "2_2") (pintype "passive"))
    )
    (net (code "27") (name "Net-(R22-Pad2)") (class "Default")
      (node (ref "R22") (pin "2") (pinfunction "2_2") (pintype "passive"))
      (node (ref "R24") (pin "1") (pinfunction "1_1") (pintype "passive"))
    )
    (net (code "28") (name "Net-(TR1-B)") (class "Default")
      (node (ref "R15") (pin "1") (pinfunction "1_1") (pintype "passive"))
      (node (ref "TR1") (pin "1") (pinfunction "B_1") (pintype "bidirectional"))
      (node (ref "TR2") (pin "3") (pinfunction "C_3") (pintype "bidirectional"))
    )
    (net (code "29") (name "Net-(TR2-B)") (class "Default")
      (node (ref "C14") (pin "2") (pinfunction "2_2") (pintype "passive"))
      (node (ref "R30") (pin "1") (pinfunction "1_1") (pintype "passive"))
      (node (ref "TR2") (pin "1") (pinfunction "B_1") (pintype "bidirectional"))
    )
    (net (code "30") (name "Net-(TR2-E)") (class "Default")
      (node (ref "R32") (pin "2") (pinfunction "2_2") (pintype "passive"))
      (node (ref "TR2") (pin "2") (pinfunction "E_2") (pintype "bidirectional"))
    )
    (net (code "31") (name "Net-(TR3-B)") (class "Default")
      (node (ref "R31") (pin "2") (pinfunction "2_2") (pintype "passive"))
      (node (ref "TR3") (pin "1") (pinfunction "B_1") (pintype "bidirectional"))
    )
    (net (code "32") (name "Net-(TR3-C)") (class "Default")
      (node (ref "R32") (pin "1") (pinfunction "1_1") (pintype "passive"))
      (node (ref "TR3") (pin "3") (pinfunction "C_3") (pintype "bidirectional"))
    )
    (net (code "33") (name "Net-(TR4-B)") (class "Default")
      (node (ref "C16") (pin "2") (pinfunction "2_2") (pintype "passive"))
      (node (ref "R36") (pin "1") (pinfunction "1_1") (pintype "passive"))
      (node (ref "TR4") (pin "1") (pinfunction "B_1") (pintype "bidirectional"))
    )
    (net (code "34") (name "Net-(TR4-C)") (class "Default")
      (node (ref "R35") (pin "1") (pinfunction "1_1") (pintype "passive"))
      (node (ref "TR4") (pin "3") (pinfunction "C_3") (pintype "bidirectional"))
      (node (ref "TR7") (pin "1") (pinfunction "B_1") (pintype "bidirectional"))
    )
    (net (code "35") (name "Net-(TR4-E)") (class "Default")
      (node (ref "R34") (pin "2") (pinfunction "2_2") (pintype "passive"))
      (node (ref "TR4") (pin "2") (pinfunction "E_2") (pintype "bidirectional"))
    )
    (net (code "36") (name "Net-(TR5-B)") (class "Default")
      (node (ref "R38") (pin "2") (pinfunction "2_2") (pintype "passive"))
      (node (ref "TR5") (pin "1") (pinfunction "B_1") (pintype "bidirectional"))
    )
    (net (code "37") (name "Net-(TR5-C)") (class "Default")
      (node (ref "R34") (pin "1") (pinfunction "1_1") (pintype "passive"))
      (node (ref "TR5") (pin "3") (pinfunction "C_3") (pintype "bidirectional"))
    )
    (net (code "38") (name "Net-(TR6-B)") (class "Default")
      (node (ref "R8") (pin "2") (pinfunction "2_2") (pintype "passive"))
      (node (ref "TR6") (pin "1") (pinfunction "B_1") (pintype "bidirectional"))
    )
    (net (code "39") (name "PIN21_ENC_B1_B") (class "Default")
      (node (ref "ENC_B1") (pin "B1") (pinfunction "B1_B1") (pintype "bidirectional"))
      (node (ref "IC1") (pin "21") (pinfunction "RD2/PSP2_21") (pintype "bidirectional"))
      (node (ref "R6") (pin "2") (pinfunction "2_2") (pintype "passive"))
    )
    (net (code "40") (name "PIN22_ENC_B1_A") (class "Default")
      (node (ref "ENC_B1") (pin "A1") (pinfunction "A1_A1") (pintype "bidirectional"))
      (node (ref "IC1") (pin "22") (pinfunction "RD3/PSP3_22") (pintype "bidirectional"))
      (node (ref "R7") (pin "1") (pinfunction "1_1") (pintype "passive"))
    )
    (net (code "41") (name "PIN27_ENC_B_ADJ_B") (class "Default")
      (node (ref "ENC_B") (pin "B1") (pinfunction "B1_B1") (pintype "bidirectional"))
      (node (ref "IC1") (pin "27") (pinfunction "RD4/PSP4_27") (pintype "bidirectional"))
      (node (ref "R4") (pin "1") (pinfunction "1_1") (pintype "passive"))
    )
    (net (code "42") (name "PIN28_ENC_B_ADJ_A") (class "Default")
      (node (ref "ENC_B") (pin "A1") (pinfunction "A1_A1") (pintype "bidirectional"))
      (node (ref "IC1") (pin "28") (pinfunction "RD5/PSP5/P1B_28") (pintype "bidirectional"))
      (node (ref "R5") (pin "1") (pinfunction "1_1") (pintype "passive"))
    )
    (net (code "43") (name "PIN_16_MCU") (class "Default")
      (node (ref "IC1") (pin "16") (pinfunction "RC1/T1OSI/CCP2_16") (pintype "bidirectional"))
      (node (ref "R3") (pin "1") (pinfunction "1_1") (pintype "passive"))
      (node (ref "R30") (pin "2") (pinfunction "2_2") (pintype "passive"))
    )
    (net (code "44") (name "PIN_17_MCU") (class "Default")
      (node (ref "IC1") (pin "17") (pinfunction "RC2/CCP1/P1A_17") (pintype "bidirectional"))
      (node (ref "R12") (pin "1") (pinfunction "1_1") (pintype "passive"))
      (node (ref "R36") (pin "2") (pinfunction "2_2") (pintype "passive"))
    )
    (net (code "45") (name "PIN_18_MCU") (class "Default")
      (node (ref "IC1") (pin "18") (pinfunction "RC3/SCK/SCL_18") (pintype "bidirectional"))
      (node (ref "R38") (pin "1") (pinfunction "1_1") (pintype "passive"))
    )
    (net (code "46") (name "PIN_19_ENC_A_A") (class "Default")
      (node (ref "ENC_A") (pin "A1") (pinfunction "A1_A1") (pintype "bidirectional"))
      (node (ref "IC1") (pin "20") (pinfunction "RD1/PSP1_20") (pintype "bidirectional"))
      (node (ref "R2") (pin "2") (pinfunction "2_2") (pintype "passive"))
    )
    (net (code "47") (name "PIN_19_ENC_A_B") (class "Default")
      (node (ref "ENC_A") (pin "B1") (pinfunction "B1_B1") (pintype "bidirectional"))
      (node (ref "IC1") (pin "19") (pinfunction "RD0/PSP0_19") (pintype "bidirectional"))
      (node (ref "R3_1") (pin "2") (pinfunction "2_2") (pintype "passive"))
    )
    (net (code "48") (name "PIN_23_MCU") (class "Default")
      (node (ref "IC1") (pin "23") (pinfunction "RC4/SDI/SDA_23") (pintype "bidirectional"))
      (node (ref "R31") (pin "1") (pinfunction "1_1") (pintype "passive"))
    )
    (net (code "49") (name "PIN_24_MCU") (class "Default")
      (node (ref "IC1") (pin "24") (pinfunction "RC5/SDO_24") (pintype "bidirectional"))
      (node (ref "R8") (pin "1") (pinfunction "1_1") (pintype "passive"))
    )
    (net (code "50") (name "unconnected-(ENC_A-PadMH1)") (class "Default")
      (node (ref "ENC_A") (pin "MH1") (pinfunction "MH1_MH1") (pintype "bidirectional"))
    )
    (net (code "51") (name "unconnected-(ENC_A-PadMH2)") (class "Default")
      (node (ref "ENC_A") (pin "MH2") (pinfunction "MH2_MH2") (pintype "bidirectional"))
    )
    (net (code "52") (name "unconnected-(ENC_B-PadMH1)") (class "Default")
      (node (ref "ENC_B") (pin "MH1") (pinfunction "MH1_MH1") (pintype "bidirectional"))
    )
    (net (code "53") (name "unconnected-(ENC_B-PadMH2)") (class "Default")
      (node (ref "ENC_B") (pin "MH2") (pinfunction "MH2_MH2") (pintype "bidirectional"))
    )
    (net (code "54") (name "unconnected-(ENC_B1-PadMH1)") (class "Default")
      (node (ref "ENC_B1") (pin "MH1") (pinfunction "MH1_MH1") (pintype "bidirectional"))
    )
    (net (code "55") (name "unconnected-(ENC_B1-PadMH2)") (class "Default")
      (node (ref "ENC_B1") (pin "MH2") (pinfunction "MH2_MH2") (pintype "bidirectional"))
    )
    (net (code "56") (name "unconnected-(IC1-OSC1{slash}CLKI{slash}RA7-Pad13)") (class "Default")
      (node (ref "IC1") (pin "13") (pinfunction "OSC1/CLKI/RA7_13") (pintype "bidirectional"))
    )
    (net (code "57") (name "unconnected-(IC1-OSC2{slash}CLKO{slash}RA6-Pad14)") (class "Default")
      (node (ref "IC1") (pin "14") (pinfunction "OSC2/CLKO/RA6_14") (pintype "bidirectional"))
    )
    (net (code "58") (name "unconnected-(IC1-RA4{slash}T0CKI{slash}C1OUT-Pad6)") (class "Default")
      (node (ref "IC1") (pin "6") (pinfunction "RA4/T0CKI/C1OUT_6") (pintype "bidirectional"))
    )
    (net (code "59") (name "unconnected-(IC1-RA5{slash}AN4{slash}~{SS}{slash}HLVDIN{slash}C2OUT-Pad7)") (class "Default")
      (node (ref "IC1") (pin "7") (pinfunction "RA5/AN4/~{SS}/HLVDIN/C2OUT_7") (pintype "bidirectional"))
    )
    (net (code "60") (name "unconnected-(IC1-RB0{slash}INT0{slash}FLT0{slash}AN12-Pad33)") (class "Default")
      (node (ref "IC1") (pin "33") (pinfunction "RB0/INT0/FLT0/AN12_33") (pintype "bidirectional"))
    )
    (net (code "61") (name "unconnected-(IC1-RB1{slash}INT1{slash}AN10-Pad34)") (class "Default")
      (node (ref "IC1") (pin "34") (pinfunction "RB1/INT1/AN10_34") (pintype "bidirectional"))
    )
    (net (code "62") (name "unconnected-(IC1-RB2{slash}INT2{slash}AN8-Pad35)") (class "Default")
      (node (ref "IC1") (pin "35") (pinfunction "RB2/INT2/AN8_35") (pintype "bidirectional"))
    )
    (net (code "63") (name "unconnected-(IC1-RB3{slash}AN9{slash}CCP2-Pad36)") (class "Default")
      (node (ref "IC1") (pin "36") (pinfunction "RB3/AN9/CCP2_36") (pintype "bidirectional"))
    )
    (net (code "64") (name "unconnected-(IC1-RB4{slash}KBI0{slash}AN11-Pad37)") (class "Default")
      (node (ref "IC1") (pin "37") (pinfunction "RB4/KBI0/AN11_37") (pintype "bidirectional"))
    )
    (net (code "65") (name "unconnected-(IC1-RB5{slash}KBI1{slash}PGM-Pad38)") (class "Default")
      (node (ref "IC1") (pin "38") (pinfunction "RB5/KBI1/PGM_38") (pintype "bidirectional"))
    )
    (net (code "66") (name "unconnected-(IC1-RB6{slash}KBI2{slash}PGC-Pad39)") (class "Default")
      (node (ref "IC1") (pin "39") (pinfunction "RB6/KBI2/PGC_39") (pintype "bidirectional"))
    )
    (net (code "67") (name "unconnected-(IC1-RB7{slash}KBI3{slash}PGD-Pad40)") (class "Default")
      (node (ref "IC1") (pin "40") (pinfunction "RB7/KBI3/PGD_40") (pintype "bidirectional"))
    )
    (net (code "68") (name "unconnected-(IC1-RC0{slash}T1OSO{slash}T13CKI-Pad15)") (class "Default")
      (node (ref "IC1") (pin "15") (pinfunction "RC0/T1OSO/T13CKI_15") (pintype "bidirectional"))
    )
    (net (code "69") (name "unconnected-(IC1-RC6{slash}TX{slash}CK-Pad25)") (class "Default")
      (node (ref "IC1") (pin "25") (pinfunction "RC6/TX/CK_25") (pintype "bidirectional"))
    )
    (net (code "70") (name "unconnected-(IC1-RC7{slash}RX{slash}DT-Pad26)") (class "Default")
      (node (ref "IC1") (pin "26") (pinfunction "RC7/RX/DT_26") (pintype "bidirectional"))
    )
    (net (code "71") (name "unconnected-(IC1-RD6{slash}PSP6{slash}P1C-Pad29)") (class "Default")
      (node (ref "IC1") (pin "29") (pinfunction "RD6/PSP6/P1C_29") (pintype "bidirectional"))
    )
    (net (code "72") (name "unconnected-(IC1-RD7{slash}PSP7{slash}P1D-Pad30)") (class "Default")
      (node (ref "IC1") (pin "30") (pinfunction "RD7/PSP7/P1D_30") (pintype "bidirectional"))
    )
    (net (code "73") (name "unconnected-(IC1-RE0{slash}~{RD}{slash}AN5-Pad8)") (class "Default")
      (node (ref "IC1") (pin "8") (pinfunction "RE0/~{RD}/AN5_8") (pintype "bidirectional"))
    )
    (net (code "74") (name "unconnected-(IC1-RE1{slash}~{WR}{slash}AN6-Pad9)") (class "Default")
      (node (ref "IC1") (pin "9") (pinfunction "RE1/~{WR}/AN6_9") (pintype "bidirectional"))
    )
    (net (code "75") (name "unconnected-(IC1-RE2{slash}~{CS}{slash}AN7-Pad10)") (class "Default")
      (node (ref "IC1") (pin "10") (pinfunction "RE2/~{CS}/AN7_10") (pintype "bidirectional"))
    )
    (net (code "76") (name "unconnected-(IC2-1IN+-Pad3)") (class "Default")
      (node (ref "IC2") (pin "3") (pinfunction "1IN+_3") (pintype "bidirectional"))
    )
    (net (code "77") (name "unconnected-(IC2-4OUT-Pad14)") (class "Default")
      (node (ref "IC2") (pin "14") (pinfunction "4OUT_14") (pintype "bidirectional"))
    )
    (net (code "78") (name "unconnected-(IC2-VCC-Pad4)") (class "Default")
      (node (ref "IC2") (pin "4") (pinfunction "VCC_4") (pintype "bidirectional"))
    )
    (net (code "79") (name "unconnected-(IC3-NC-Pad4)") (class "Default")
      (node (ref "IC3") (pin "4") (pinfunction "NC_4") (pintype "no_connect"))
    )
    (net (code "80") (name "unconnected-(J1-TIP-Pad2)") (class "Default")
      (node (ref "J1") (pin "2") (pinfunction "TIP_2") (pintype "bidirectional"))
    )
    (net (code "81") (name "unconnected-(J2-TIP-Pad2)") (class "Default")
      (node (ref "J2") (pin "2") (pinfunction "TIP_2") (pintype "bidirectional"))
    )
    (net (code "82") (name "unconnected-(R11-S-Pad2)") (class "Default")
      (node (ref "R11") (pin "2") (pinfunction "S_2") (pintype "passive"))
    )
    (net (code "83") (name "unconnected-(R22-Pad1)") (class "Default")
      (node (ref "R22") (pin "1") (pinfunction "1_1") (pintype "passive"))
    )
    (net (code "84") (name "unconnected-(S1-NC-Pad1)") (class "Default")
      (node (ref "S1") (pin "1") (pinfunction "NC_1") (pintype "no_connect"))
    )
    (net (code "85") (name "unconnected-(S1-PadMH1)") (class "Default")
      (node (ref "S1") (pin "MH1") (pinfunction "MH1_MH1") (pintype "bidirectional"))
    )
    (net (code "86") (name "unconnected-(S1-PadMH2)") (class "Default")
      (node (ref "S1") (pin "MH2") (pinfunction "MH2_MH2") (pintype "bidirectional"))
    )
    (net (code "87") (name "unconnected-(T1-SEC1+{slash}2--Pad4)") (class "Default")
      (node (ref "T1") (pin "4") (pinfunction "SEC1+/2-_4") (pintype "bidirectional"))
    )
    (net (code "88") (name "unconnected-(T2-SEC1+{slash}2--Pad4)") (class "Default")
      (node (ref "T2") (pin "4") (pinfunction "SEC1+/2-_4") (pintype "bidirectional"))
    )
    (net (code "89") (name "unconnected-(TR6-C-Pad3)") (class "Default")
      (node (ref "TR6") (pin "3") (pinfunction "C_3") (pintype "bidirectional"))
    )
  )
)
